# Tracker_V1.net
KiCad netlist of a schematic drawn in EAGLE
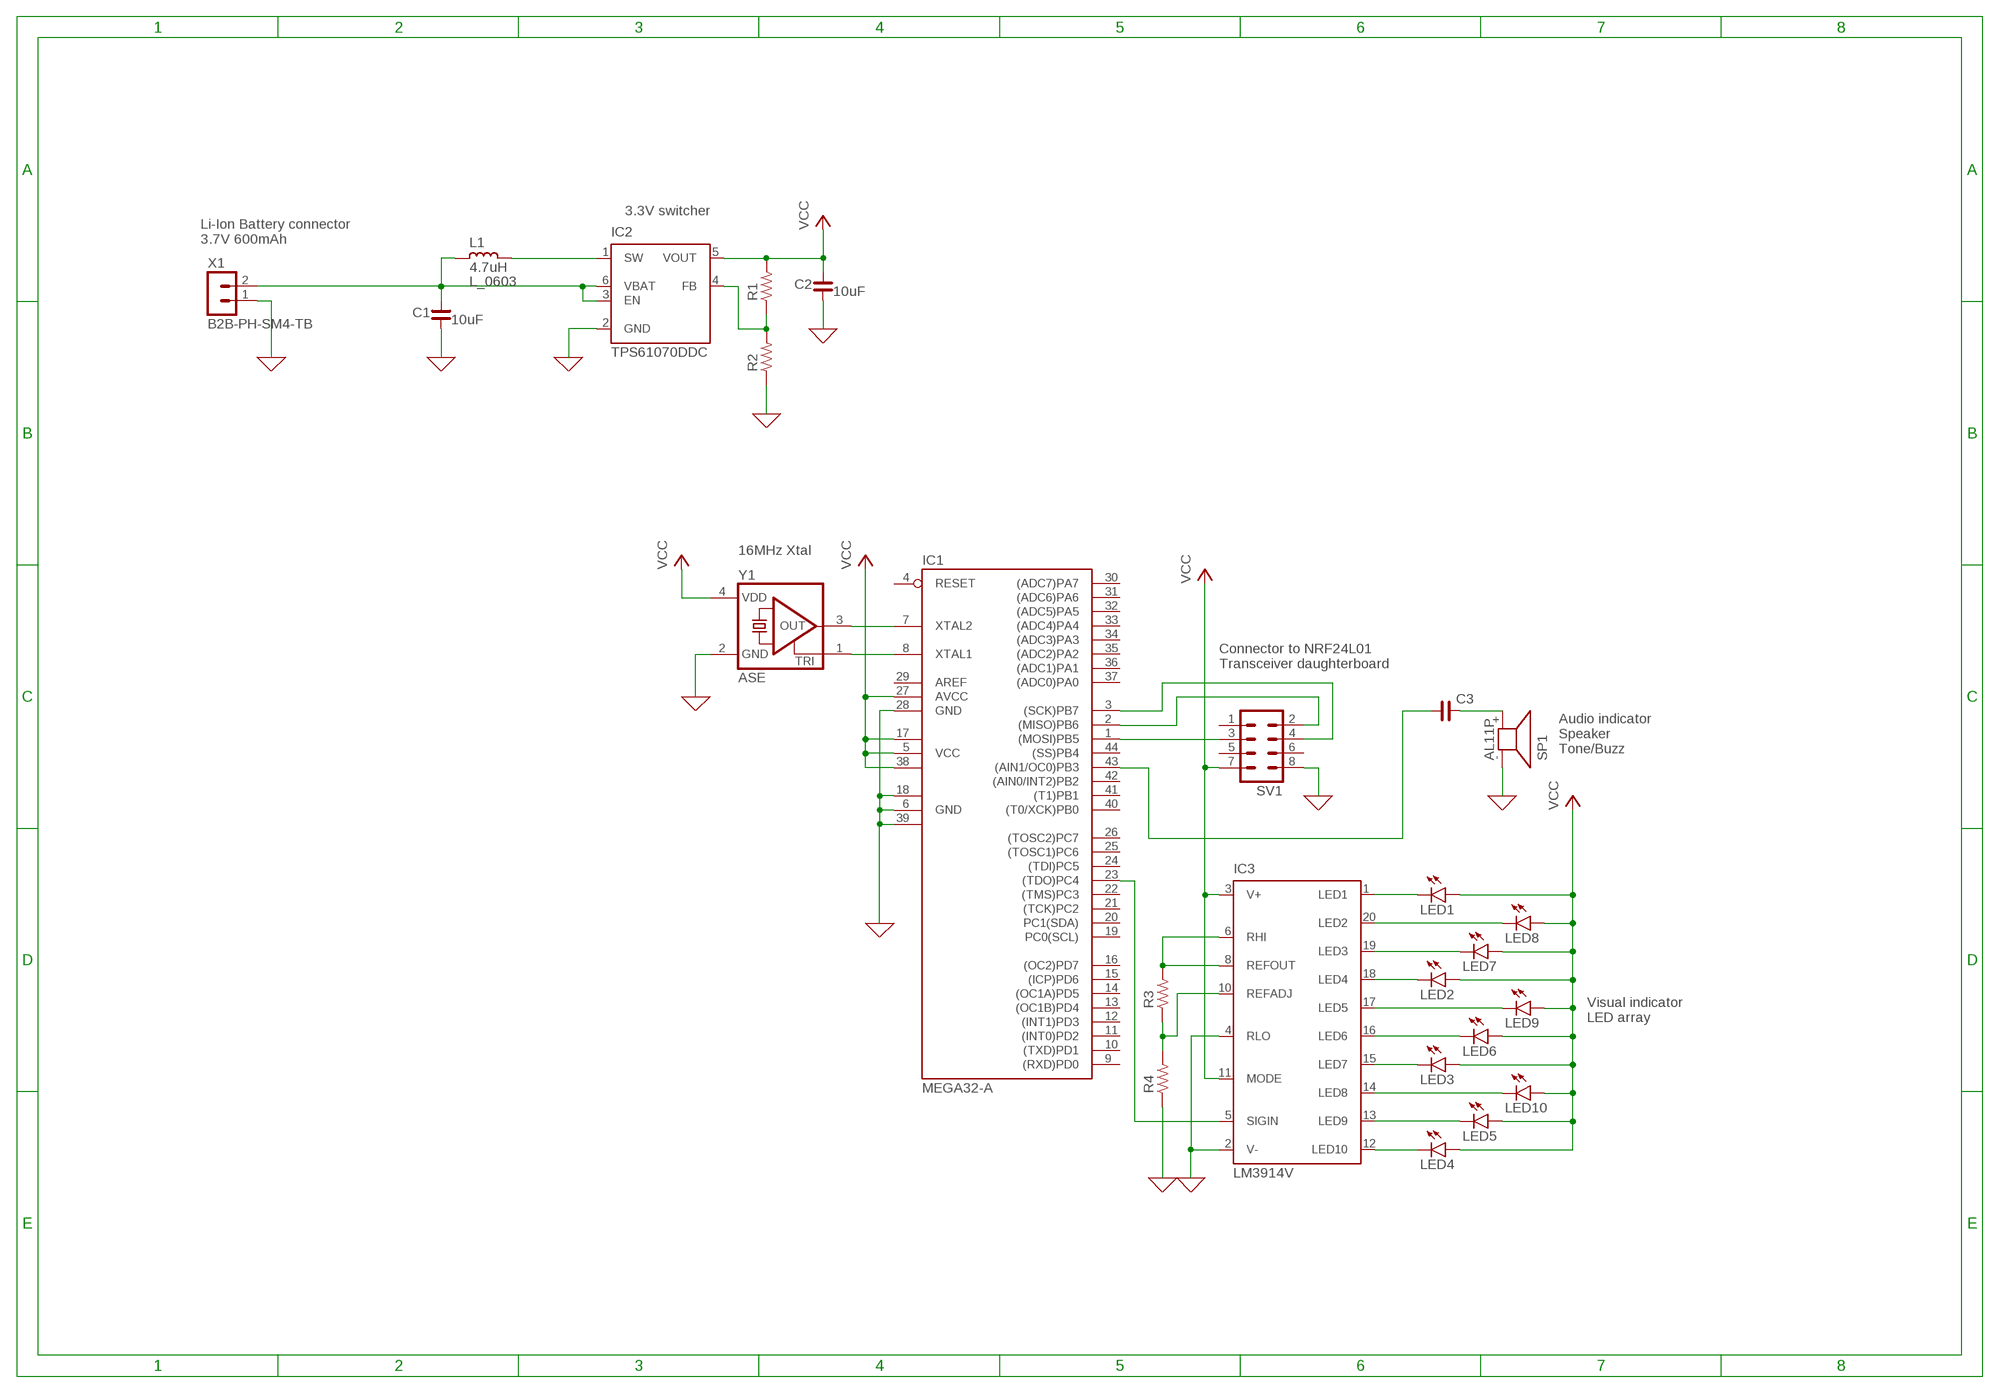
[diagram p0: schematic, sheet 1]

(export (version "E")
  (design (tool "Eeschema 10.0.6"))
  (components
    (comp (ref "C1")
      (value "C_0603")
      (footprint "eagle-import:C0603")
      (fields (field (name "C1") "10uF"))
      (libsource (lib "eagle-import") (part "C_0603"))
    )
    (comp (ref "C2")
      (value "C_0603")
      (footprint "eagle-import:C0603")
      (fields (field (name "C1") "10uF"))
      (libsource (lib "eagle-import") (part "C_0603"))
    )
    (comp (ref "C3")
      (value "C_0603")
      (footprint "eagle-import:C0603")
      (libsource (lib "eagle-import") (part "C_0603"))
    )
    (comp (ref "IC1")
      (value "MEGA32-A")
      (footprint "eagle-import:TQFP44")
      (fields (field (name "MPN") "ATMEGA32-16AU"))
      (libsource (lib "eagle-import") (part "MEGA32-A"))
    )
    (comp (ref "IC2")
      (value "TPS61070DDC")
      (footprint "eagle-import:TSOT23-6_DDC")
      (fields (field (name "MPN") "TPS61070DDCR"))
      (libsource (lib "eagle-import") (part "TPS6107DDC0"))
    )
    (comp (ref "IC3")
      (value "LM3914V")
      (footprint "eagle-import:PLCC20S")
      (libsource (lib "eagle-import") (part "LM391V4"))
    )
    (comp (ref "L1")
      (value "L_0603")
      (footprint "eagle-import:L0603")
      (fields (field (name "L1") "4.7uH"))
      (libsource (lib "eagle-import") (part "L_0603"))
    )
    (comp (ref "LED1")
      (value "LEDCHIP-LED0603")
      (footprint "eagle-import:CHIP-LED0603")
      (libsource (lib "eagle-import") (part "LEDCHIP-LED0603"))
    )
    (comp (ref "LED2")
      (value "LEDCHIP-LED0603")
      (footprint "eagle-import:CHIP-LED0603")
      (libsource (lib "eagle-import") (part "LEDCHIP-LED0603"))
    )
    (comp (ref "LED3")
      (value "LEDCHIP-LED0603")
      (footprint "eagle-import:CHIP-LED0603")
      (libsource (lib "eagle-import") (part "LEDCHIP-LED0603"))
    )
    (comp (ref "LED4")
      (value "LEDCHIP-LED0603")
      (footprint "eagle-import:CHIP-LED0603")
      (libsource (lib "eagle-import") (part "LEDCHIP-LED0603"))
    )
    (comp (ref "LED5")
      (value "LEDCHIP-LED0603")
      (footprint "eagle-import:CHIP-LED0603")
      (libsource (lib "eagle-import") (part "LEDCHIP-LED0603"))
    )
    (comp (ref "LED6")
      (value "LEDCHIP-LED0603")
      (footprint "eagle-import:CHIP-LED0603")
      (libsource (lib "eagle-import") (part "LEDCHIP-LED0603"))
    )
    (comp (ref "LED7")
      (value "LEDCHIP-LED0603")
      (footprint "eagle-import:CHIP-LED0603")
      (libsource (lib "eagle-import") (part "LEDCHIP-LED0603"))
    )
    (comp (ref "LED8")
      (value "LEDCHIP-LED0603")
      (footprint "eagle-import:CHIP-LED0603")
      (libsource (lib "eagle-import") (part "LEDCHIP-LED0603"))
    )
    (comp (ref "LED9")
      (value "LEDCHIP-LED0603")
      (footprint "eagle-import:CHIP-LED0603")
      (libsource (lib "eagle-import") (part "LEDCHIP-LED0603"))
    )
    (comp (ref "LED10")
      (value "LEDCHIP-LED0603")
      (footprint "eagle-import:CHIP-LED0603")
      (libsource (lib "eagle-import") (part "LEDCHIP-LED0603"))
    )
    (comp (ref "R1")
      (value "R_0603")
      (footprint "eagle-import:R0603")
      (libsource (lib "eagle-import") (part "R_0603"))
    )
    (comp (ref "R2")
      (value "R_0603")
      (footprint "eagle-import:R0603")
      (libsource (lib "eagle-import") (part "R_0603"))
    )
    (comp (ref "R3")
      (value "R_0603")
      (footprint "eagle-import:R0603")
      (libsource (lib "eagle-import") (part "R_0603"))
    )
    (comp (ref "R4")
      (value "R_0603")
      (footprint "eagle-import:R0603")
      (libsource (lib "eagle-import") (part "R_0603"))
    )
    (comp (ref "SP1")
      (value "AL11P")
      (footprint "eagle-import:AL11P")
      (libsource (lib "eagle-import") (part "AL11P"))
    )
    (comp (ref "SV1")
      (value "MA04-2")
      (footprint "eagle-import:MA04-2")
      (libsource (lib "eagle-import") (part "MA04-2"))
    )
    (comp (ref "X1")
      (value "B2B-PH-SM4-TB")
      (footprint "eagle-import:B2B-PH-SM4-TB")
      (libsource (lib "eagle-import") (part "B2B-PH-SM4-TB"))
    )
    (comp (ref "Y1")
      (value "ASE")
      (footprint "eagle-import:ASE")
      (libsource (lib "eagle-import") (part "ASE"))
    )
  )
  (nets
    (net (code "1") (name "GND") (class "Default")
      (node (ref "C1") (pin "1") (pinfunction "1_1") (pintype "passive"))
      (node (ref "C2") (pin "1") (pinfunction "1_1") (pintype "passive"))
      (node (ref "IC1") (pin "18") (pinfunction "GND1_18") (pintype "power_in"))
      (node (ref "IC1") (pin "28") (pinfunction "GND_28") (pintype "power_in"))
      (node (ref "IC1") (pin "39") (pinfunction "GND2_39") (pintype "power_in"))
      (node (ref "IC1") (pin "6") (pinfunction "GND_6") (pintype "power_in"))
      (node (ref "IC2") (pin "2") (pinfunction "GND_2") (pintype "power_in"))
      (node (ref "IC3") (pin "2") (pinfunction "V-_2") (pintype "power_in"))
      (node (ref "IC3") (pin "4") (pinfunction "RLO_4") (pintype "input"))
      (node (ref "R2") (pin "1") (pinfunction "1_1") (pintype "passive"))
      (node (ref "R4") (pin "1") (pinfunction "1_1") (pintype "passive"))
      (node (ref "SP1") (pin "-") (pinfunction "1_-") (pintype "passive"))
      (node (ref "SV1") (pin "8") (pinfunction "8_8") (pintype "passive"))
      (node (ref "X1") (pin "1") (pinfunction "1_1") (pintype "passive"))
      (node (ref "Y1") (pin "2") (pinfunction "GND_2") (pintype "power_in"))
    )
    (net (code "2") (name "Net-(IC1-(AIN1{slash}OC0)PB3)") (class "Default")
      (node (ref "C3") (pin "1") (pinfunction "1_1") (pintype "passive"))
      (node (ref "IC1") (pin "43") (pinfunction "(AIN1/OC0)PB3_43") (pintype "bidirectional"))
    )
    (net (code "3") (name "Net-(IC1-(MISO)PB6)") (class "Default")
      (node (ref "IC1") (pin "2") (pinfunction "(MISO)PB6_2") (pintype "bidirectional"))
      (node (ref "SV1") (pin "2") (pinfunction "2_2") (pintype "passive"))
    )
    (net (code "4") (name "Net-(IC1-(MOSI)PB5)") (class "Default")
      (node (ref "IC1") (pin "1") (pinfunction "(MOSI)PB5_1") (pintype "bidirectional"))
      (node (ref "SV1") (pin "3") (pinfunction "3_3") (pintype "passive"))
    )
    (net (code "5") (name "Net-(IC1-(SCK)PB7)") (class "Default")
      (node (ref "IC1") (pin "3") (pinfunction "(SCK)PB7_3") (pintype "bidirectional"))
      (node (ref "SV1") (pin "4") (pinfunction "4_4") (pintype "passive"))
    )
    (net (code "6") (name "Net-(IC1-(TDO)PC4)") (class "Default")
      (node (ref "IC1") (pin "23") (pinfunction "(TDO)PC4_23") (pintype "bidirectional"))
      (node (ref "IC3") (pin "5") (pinfunction "SIGIN_5") (pintype "input"))
    )
    (net (code "7") (name "Net-(IC1-XTAL1)") (class "Default")
      (node (ref "IC1") (pin "8") (pinfunction "XTAL1_8") (pintype "bidirectional"))
      (node (ref "Y1") (pin "1") (pinfunction "TRI_1") (pintype "input"))
    )
    (net (code "8") (name "Net-(IC1-XTAL2)") (class "Default")
      (node (ref "IC1") (pin "7") (pinfunction "XTAL2_7") (pintype "bidirectional"))
      (node (ref "Y1") (pin "3") (pinfunction "OUT_3") (pintype "output"))
    )
    (net (code "9") (name "Net-(IC2-EN)") (class "Default")
      (node (ref "C1") (pin "2") (pinfunction "2_2") (pintype "passive"))
      (node (ref "IC2") (pin "3") (pinfunction "EN_3") (pintype "input"))
      (node (ref "IC2") (pin "6") (pinfunction "VBAT_6") (pintype "input"))
      (node (ref "L1") (pin "2") (pinfunction "2_2") (pintype "passive"))
      (node (ref "X1") (pin "2") (pinfunction "2_2") (pintype "passive"))
    )
    (net (code "10") (name "Net-(IC2-FB)") (class "Default")
      (node (ref "IC2") (pin "4") (pinfunction "FB_4") (pintype "input"))
      (node (ref "R1") (pin "1") (pinfunction "1_1") (pintype "passive"))
      (node (ref "R2") (pin "2") (pinfunction "2_2") (pintype "passive"))
    )
    (net (code "11") (name "Net-(IC2-SW)") (class "Default")
      (node (ref "IC2") (pin "1") (pinfunction "SW_1") (pintype "input"))
      (node (ref "L1") (pin "1") (pinfunction "1_1") (pintype "passive"))
    )
    (net (code "12") (name "Net-(IC3-LED1)") (class "Default")
      (node (ref "IC3") (pin "1") (pinfunction "LED1_1") (pintype "output"))
      (node (ref "LED1") (pin "C") (pinfunction "C_C") (pintype "passive"))
    )
    (net (code "13") (name "Net-(IC3-LED2)") (class "Default")
      (node (ref "IC3") (pin "20") (pinfunction "LED2_20") (pintype "output"))
      (node (ref "LED8") (pin "C") (pinfunction "C_C") (pintype "passive"))
    )
    (net (code "14") (name "Net-(IC3-LED3)") (class "Default")
      (node (ref "IC3") (pin "19") (pinfunction "LED3_19") (pintype "output"))
      (node (ref "LED7") (pin "C") (pinfunction "C_C") (pintype "passive"))
    )
    (net (code "15") (name "Net-(IC3-LED4)") (class "Default")
      (node (ref "IC3") (pin "18") (pinfunction "LED4_18") (pintype "output"))
      (node (ref "LED2") (pin "C") (pinfunction "C_C") (pintype "passive"))
    )
    (net (code "16") (name "Net-(IC3-LED5)") (class "Default")
      (node (ref "IC3") (pin "17") (pinfunction "LED5_17") (pintype "output"))
      (node (ref "LED9") (pin "C") (pinfunction "C_C") (pintype "passive"))
    )
    (net (code "17") (name "Net-(IC3-LED6)") (class "Default")
      (node (ref "IC3") (pin "16") (pinfunction "LED6_16") (pintype "output"))
      (node (ref "LED6") (pin "C") (pinfunction "C_C") (pintype "passive"))
    )
    (net (code "18") (name "Net-(IC3-LED7)") (class "Default")
      (node (ref "IC3") (pin "15") (pinfunction "LED7_15") (pintype "output"))
      (node (ref "LED3") (pin "C") (pinfunction "C_C") (pintype "passive"))
    )
    (net (code "19") (name "Net-(IC3-LED8)") (class "Default")
      (node (ref "IC3") (pin "14") (pinfunction "LED8_14") (pintype "output"))
      (node (ref "LED10") (pin "C") (pinfunction "C_C") (pintype "passive"))
    )
    (net (code "20") (name "Net-(IC3-LED9)") (class "Default")
      (node (ref "IC3") (pin "13") (pinfunction "LED9_13") (pintype "output"))
      (node (ref "LED5") (pin "C") (pinfunction "C_C") (pintype "passive"))
    )
    (net (code "21") (name "Net-(IC3-LED10)") (class "Default")
      (node (ref "IC3") (pin "12") (pinfunction "LED10_12") (pintype "output"))
      (node (ref "LED4") (pin "C") (pinfunction "C_C") (pintype "passive"))
    )
    (net (code "22") (name "Net-(IC3-REFADJ)") (class "Default")
      (node (ref "IC3") (pin "10") (pinfunction "REFADJ_10") (pintype "passive"))
      (node (ref "R3") (pin "1") (pinfunction "1_1") (pintype "passive"))
      (node (ref "R4") (pin "2") (pinfunction "2_2") (pintype "passive"))
    )
    (net (code "23") (name "Net-(IC3-REFOUT)") (class "Default")
      (node (ref "IC3") (pin "6") (pinfunction "RHI_6") (pintype "input"))
      (node (ref "IC3") (pin "8") (pinfunction "REFOUT_8") (pintype "output"))
      (node (ref "R3") (pin "2") (pinfunction "2_2") (pintype "passive"))
    )
    (net (code "24") (name "Net-(SP1-2)") (class "Default")
      (node (ref "C3") (pin "2") (pinfunction "2_2") (pintype "passive"))
      (node (ref "SP1") (pin "+") (pinfunction "2_+") (pintype "passive"))
    )
    (net (code "25") (name "VCC") (class "Default")
      (node (ref "C2") (pin "2") (pinfunction "2_2") (pintype "passive"))
      (node (ref "IC1") (pin "17") (pinfunction "VCC1_17") (pintype "power_in"))
      (node (ref "IC1") (pin "27") (pinfunction "AVCC_27") (pintype "power_in"))
      (node (ref "IC1") (pin "38") (pinfunction "VCC2_38") (pintype "power_in"))
      (node (ref "IC1") (pin "5") (pinfunction "VCC_5") (pintype "power_in"))
      (node (ref "IC2") (pin "5") (pinfunction "VOUT_5") (pintype "passive"))
      (node (ref "IC3") (pin "11") (pinfunction "MODE_11") (pintype "input"))
      (node (ref "IC3") (pin "3") (pinfunction "V+_3") (pintype "power_in"))
      (node (ref "LED1") (pin "A") (pinfunction "A_A") (pintype "passive"))
      (node (ref "LED10") (pin "A") (pinfunction "A_A") (pintype "passive"))
      (node (ref "LED2") (pin "A") (pinfunction "A_A") (pintype "passive"))
      (node (ref "LED3") (pin "A") (pinfunction "A_A") (pintype "passive"))
      (node (ref "LED4") (pin "A") (pinfunction "A_A") (pintype "passive"))
      (node (ref "LED5") (pin "A") (pinfunction "A_A") (pintype "passive"))
      (node (ref "LED6") (pin "A") (pinfunction "A_A") (pintype "passive"))
      (node (ref "LED7") (pin "A") (pinfunction "A_A") (pintype "passive"))
      (node (ref "LED8") (pin "A") (pinfunction "A_A") (pintype "passive"))
      (node (ref "LED9") (pin "A") (pinfunction "A_A") (pintype "passive"))
      (node (ref "R1") (pin "2") (pinfunction "2_2") (pintype "passive"))
      (node (ref "SV1") (pin "7") (pinfunction "7_7") (pintype "passive"))
      (node (ref "Y1") (pin "4") (pinfunction "VDD_4") (pintype "power_in"))
    )
    (net (code "26") (name "unconnected-(IC1-(ADC0)PA0-Pad37)") (class "Default")
      (node (ref "IC1") (pin "37") (pinfunction "(ADC0)PA0_37") (pintype "bidirectional"))
    )
    (net (code "27") (name "unconnected-(IC1-(ADC1)PA1-Pad36)") (class "Default")
      (node (ref "IC1") (pin "36") (pinfunction "(ADC1)PA1_36") (pintype "bidirectional"))
    )
    (net (code "28") (name "unconnected-(IC1-(ADC2)PA2-Pad35)") (class "Default")
      (node (ref "IC1") (pin "35") (pinfunction "(ADC2)PA2_35") (pintype "bidirectional"))
    )
    (net (code "29") (name "unconnected-(IC1-(ADC3)PA3-Pad34)") (class "Default")
      (node (ref "IC1") (pin "34") (pinfunction "(ADC3)PA3_34") (pintype "bidirectional"))
    )
    (net (code "30") (name "unconnected-(IC1-(ADC4)PA4-Pad33)") (class "Default")
      (node (ref "IC1") (pin "33") (pinfunction "(ADC4)PA4_33") (pintype "bidirectional"))
    )
    (net (code "31") (name "unconnected-(IC1-(ADC5)PA5-Pad32)") (class "Default")
      (node (ref "IC1") (pin "32") (pinfunction "(ADC5)PA5_32") (pintype "bidirectional"))
    )
    (net (code "32") (name "unconnected-(IC1-(ADC6)PA6-Pad31)") (class "Default")
      (node (ref "IC1") (pin "31") (pinfunction "(ADC6)PA6_31") (pintype "bidirectional"))
    )
    (net (code "33") (name "unconnected-(IC1-(ADC7)PA7-Pad30)") (class "Default")
      (node (ref "IC1") (pin "30") (pinfunction "(ADC7)PA7_30") (pintype "bidirectional"))
    )
    (net (code "34") (name "unconnected-(IC1-(AIN0{slash}INT2)PB2-Pad42)") (class "Default")
      (node (ref "IC1") (pin "42") (pinfunction "(AIN0/INT2)PB2_42") (pintype "bidirectional"))
    )
    (net (code "35") (name "unconnected-(IC1-(ICP)PD6-Pad15)") (class "Default")
      (node (ref "IC1") (pin "15") (pinfunction "(ICP)PD6_15") (pintype "bidirectional"))
    )
    (net (code "36") (name "unconnected-(IC1-(INT0)PD2-Pad11)") (class "Default")
      (node (ref "IC1") (pin "11") (pinfunction "(INT0)PD2_11") (pintype "bidirectional"))
    )
    (net (code "37") (name "unconnected-(IC1-(INT1)PD3-Pad12)") (class "Default")
      (node (ref "IC1") (pin "12") (pinfunction "(INT1)PD3_12") (pintype "bidirectional"))
    )
    (net (code "38") (name "unconnected-(IC1-(OC1A)PD5-Pad14)") (class "Default")
      (node (ref "IC1") (pin "14") (pinfunction "(OC1A)PD5_14") (pintype "bidirectional"))
    )
    (net (code "39") (name "unconnected-(IC1-(OC1B)PD4-Pad13)") (class "Default")
      (node (ref "IC1") (pin "13") (pinfunction "(OC1B)PD4_13") (pintype "bidirectional"))
    )
    (net (code "40") (name "unconnected-(IC1-(OC2)PD7-Pad16)") (class "Default")
      (node (ref "IC1") (pin "16") (pinfunction "(OC2)PD7_16") (pintype "bidirectional"))
    )
    (net (code "41") (name "unconnected-(IC1-(RXD)PD0-Pad9)") (class "Default")
      (node (ref "IC1") (pin "9") (pinfunction "(RXD)PD0_9") (pintype "bidirectional"))
    )
    (net (code "42") (name "unconnected-(IC1-(SS)PB4-Pad44)") (class "Default")
      (node (ref "IC1") (pin "44") (pinfunction "(SS)PB4_44") (pintype "bidirectional"))
    )
    (net (code "43") (name "unconnected-(IC1-(T0{slash}XCK)PB0-Pad40)") (class "Default")
      (node (ref "IC1") (pin "40") (pinfunction "(T0/XCK)PB0_40") (pintype "bidirectional"))
    )
    (net (code "44") (name "unconnected-(IC1-(T1)PB1-Pad41)") (class "Default")
      (node (ref "IC1") (pin "41") (pinfunction "(T1)PB1_41") (pintype "bidirectional"))
    )
    (net (code "45") (name "unconnected-(IC1-(TCK)PC2-Pad21)") (class "Default")
      (node (ref "IC1") (pin "21") (pinfunction "(TCK)PC2_21") (pintype "bidirectional"))
    )
    (net (code "46") (name "unconnected-(IC1-(TDI)PC5-Pad24)") (class "Default")
      (node (ref "IC1") (pin "24") (pinfunction "(TDI)PC5_24") (pintype "bidirectional"))
    )
    (net (code "47") (name "unconnected-(IC1-(TMS)PC3-Pad22)") (class "Default")
      (node (ref "IC1") (pin "22") (pinfunction "(TMS)PC3_22") (pintype "bidirectional"))
    )
    (net (code "48") (name "unconnected-(IC1-(TOSC1)PC6-Pad25)") (class "Default")
      (node (ref "IC1") (pin "25") (pinfunction "(TOSC1)PC6_25") (pintype "bidirectional"))
    )
    (net (code "49") (name "unconnected-(IC1-(TOSC2)PC7-Pad26)") (class "Default")
      (node (ref "IC1") (pin "26") (pinfunction "(TOSC2)PC7_26") (pintype "bidirectional"))
    )
    (net (code "50") (name "unconnected-(IC1-(TXD)PD1-Pad10)") (class "Default")
      (node (ref "IC1") (pin "10") (pinfunction "(TXD)PD1_10") (pintype "bidirectional"))
    )
    (net (code "51") (name "unconnected-(IC1-AREF-Pad29)") (class "Default")
      (node (ref "IC1") (pin "29") (pinfunction "AREF_29") (pintype "passive"))
    )
    (net (code "52") (name "unconnected-(IC1-PC0(SCL)-Pad19)") (class "Default")
      (node (ref "IC1") (pin "19") (pinfunction "PC0(SCL)_19") (pintype "bidirectional"))
    )
    (net (code "53") (name "unconnected-(IC1-PC1(SDA)-Pad20)") (class "Default")
      (node (ref "IC1") (pin "20") (pinfunction "PC1(SDA)_20") (pintype "bidirectional"))
    )
    (net (code "54") (name "unconnected-(IC1-RESET-Pad4)") (class "Default")
      (node (ref "IC1") (pin "4") (pinfunction "RESET_4") (pintype "input"))
    )
    (net (code "55") (name "unconnected-(SV1-Pad1)") (class "Default")
      (node (ref "SV1") (pin "1") (pinfunction "1_1") (pintype "passive"))
    )
    (net (code "56") (name "unconnected-(SV1-Pad5)") (class "Default")
      (node (ref "SV1") (pin "5") (pinfunction "5_5") (pintype "passive"))
    )
    (net (code "57") (name "unconnected-(SV1-Pad6)") (class "Default")
      (node (ref "SV1") (pin "6") (pinfunction "6_6") (pintype "passive"))
    )
  )
)
